# 18_AUDIO_PowerAmp-AnalogT.net
KiCad netlist of a schematic drawn in Altium Designer
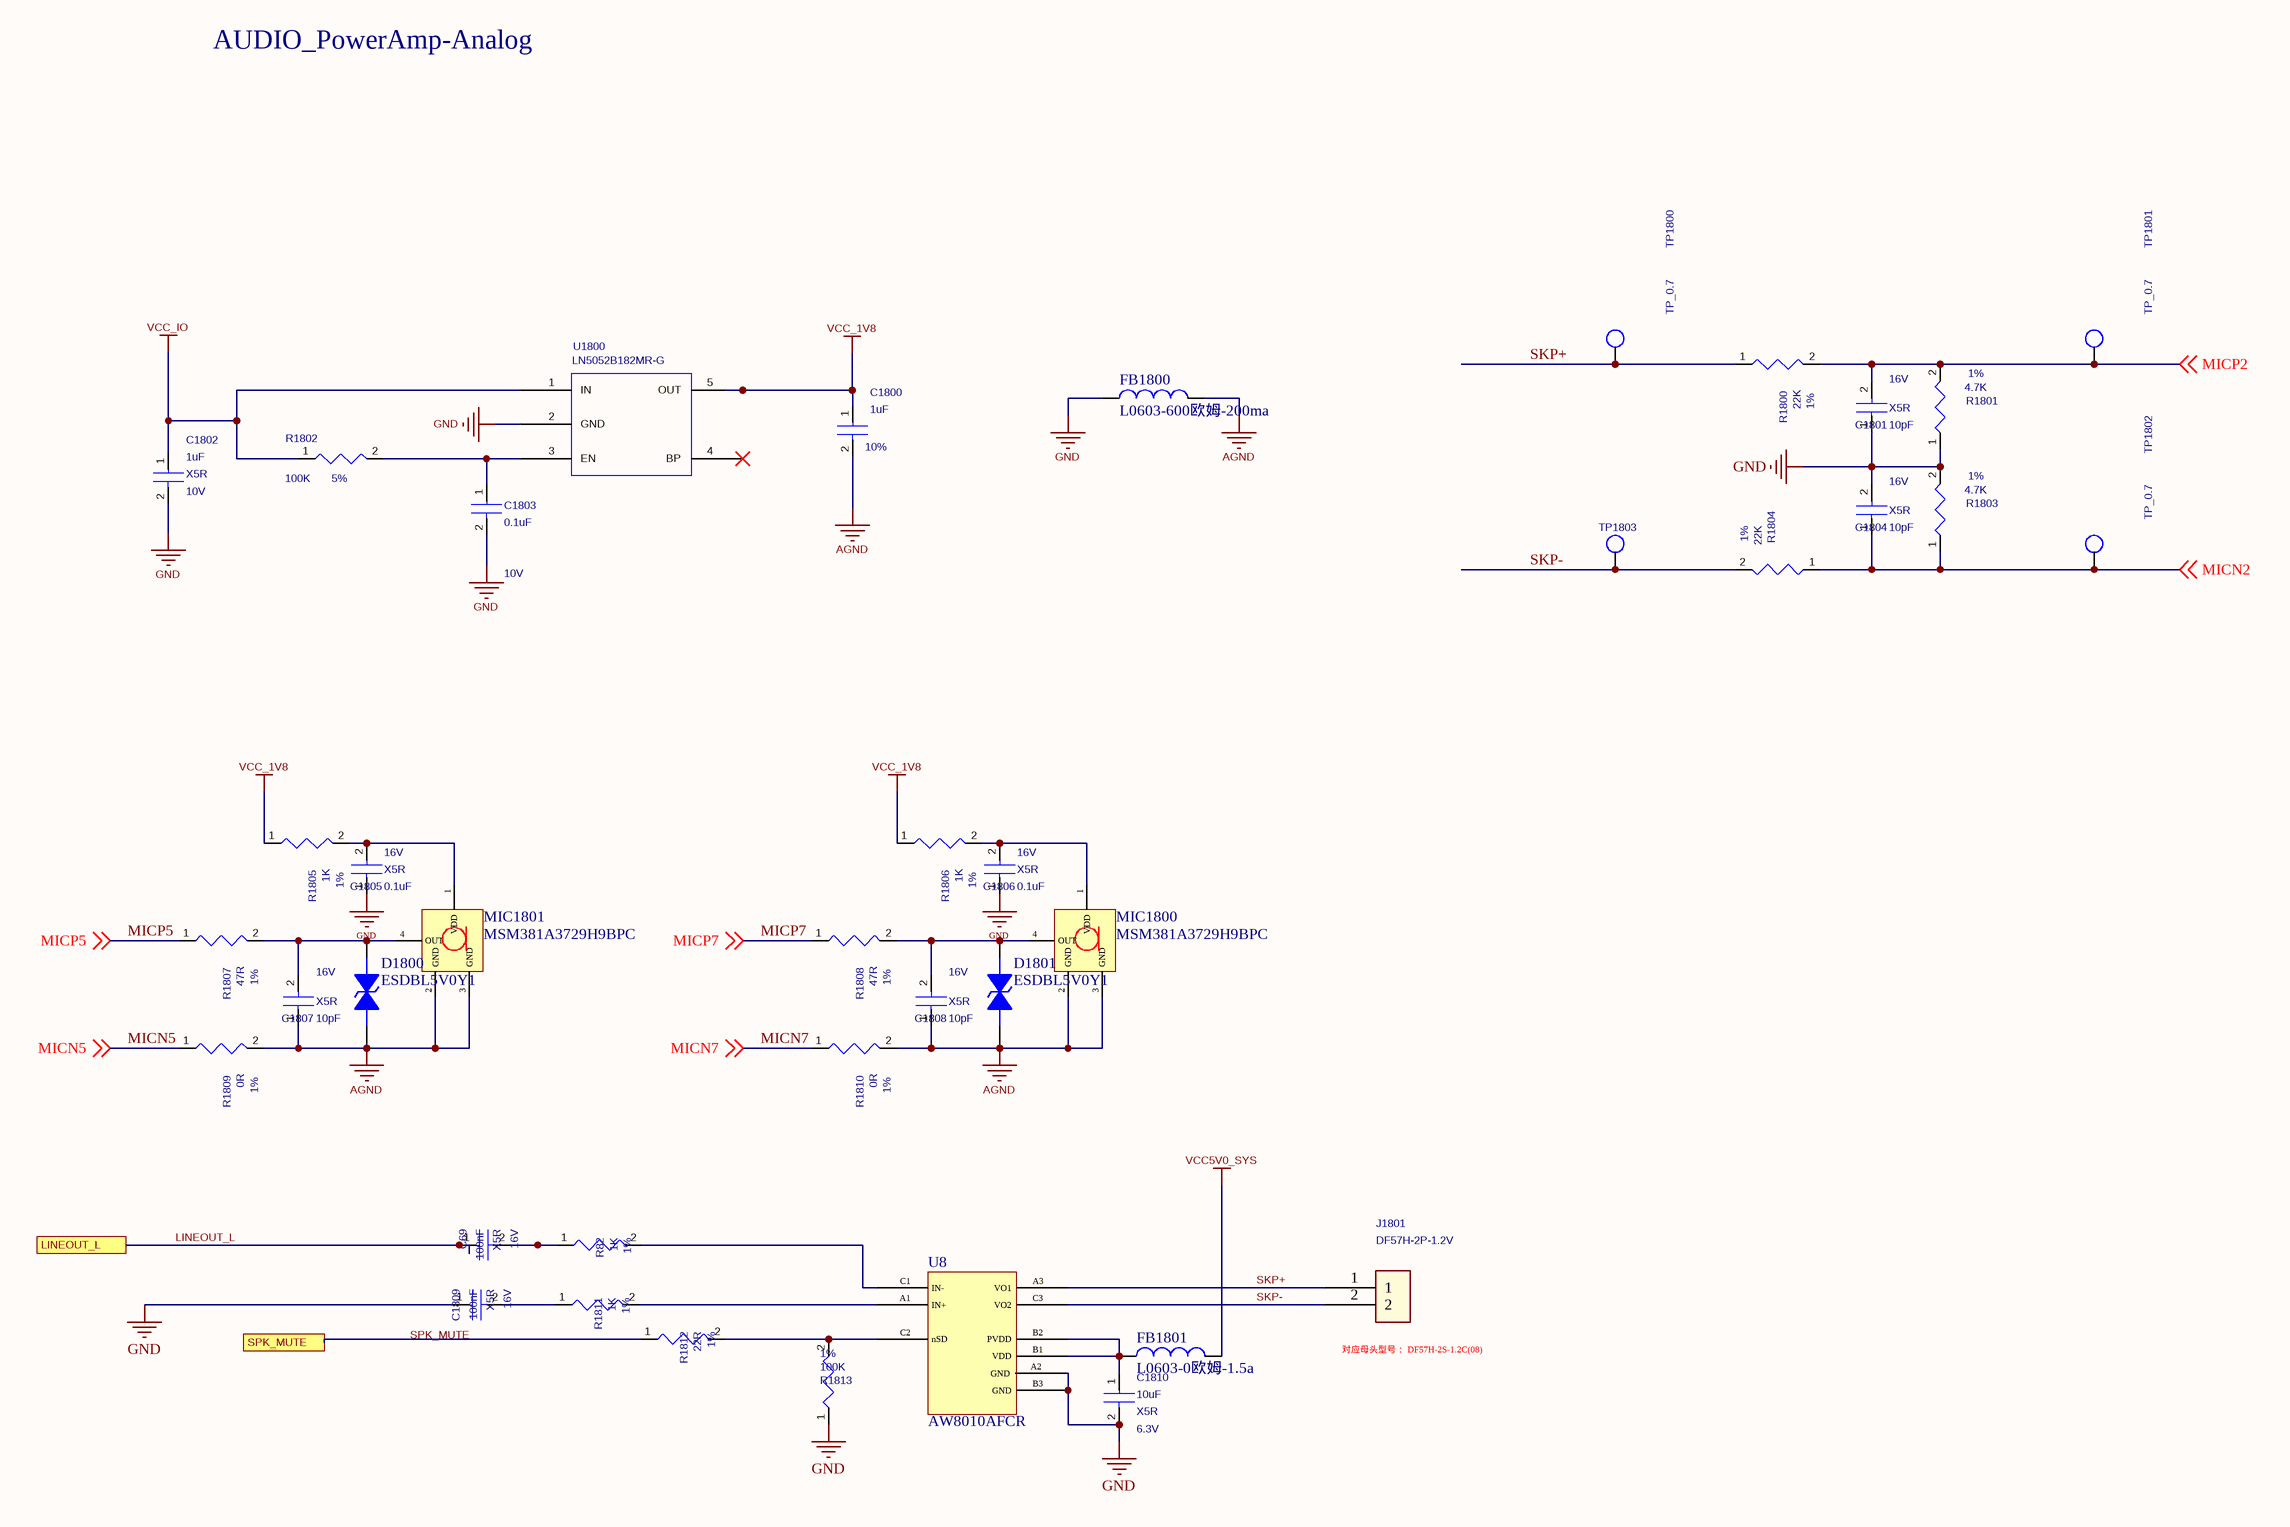
[diagram p0: 18_AUDIO_PowerAmp-AnalogT.SchDoc]

(export (version "E")
  (design (tool "Eeschema 10.0.6"))
  (components
    (comp (ref "C69")
      (value "100nF")
      (footprint "C0402")
      (description "cap,100.00nF,+/-10%,16V,X5R,C0402")
      (fields
        (field (name "MANUFACTURER") "TDK")
        (field (name "TOLERANCE") "10%")
        (field (name "VOLTAGE") "16V")
        (field (name "DIELECTRIC") "X5R")
        (field (name "CREATED_BY") "JJJ")
      )
      (libsource (lib "*") (part "CAP_NP_2"))
    )
    (comp (ref "C1800")
      (value "1uF")
      (footprint "C0402")
      (description "cap,1.00uF,+/-10%,10V,X5R,C0402")
      (fields
        (field (name "VOLTAGE") "10V")
        (field (name "MANUFACTURER") "TDK")
        (field (name "TOLERANCE") "10%")
        (field (name "CREATED_BY") "JJJ")
      )
      (libsource (lib "*") (part "CAP_NP_2"))
    )
    (comp (ref "C1801")
      (value "10pF")
      (footprint "C0402")
      (description "cap,1nF,+/-10%,16V,X5R,C0402")
      (fields
        (field (name "MANUFACTURER") "TDK")
        (field (name "TOLERANCE") "10%")
        (field (name "VOLTAGE") "16V")
        (field (name "DIELECTRIC") "X5R")
        (field (name "CREATED_BY") "JJJ")
      )
      (libsource (lib "*") (part "CAP_NP_2"))
    )
    (comp (ref "C1802")
      (value "1uF")
      (footprint "C0402")
      (description "cap,1.00uF,+/-10%,10V,X5R,C0402")
      (fields
        (field (name "VOLTAGE") "10V")
        (field (name "DIELECTRIC") "X5R")
        (field (name "TOLERANCE") "10%")
        (field (name "MANUFACTURER") "TDK")
        (field (name "CREATED_BY") "JJJ")
      )
      (libsource (lib "*") (part "CAP_NP_2"))
    )
    (comp (ref "C1803")
      (value "0.1uF")
      (footprint "C0402")
      (description "cap,0.1uF,+/-10%,10V,X5R,C0402")
      (fields
        (field (name "TOLERANCE") "10%")
        (field (name "MANUFACTURER") "TDK")
        (field (name "VOLTAGE") "10V")
        (field (name "CREATED_BY") "JJJ")
      )
      (libsource (lib "*") (part "CAP_NP_2"))
    )
    (comp (ref "C1804")
      (value "10pF")
      (footprint "C0402")
      (description "cap,1nF,+/-10%,16V,X5R,C0402")
      (fields
        (field (name "MANUFACTURER") "TDK")
        (field (name "TOLERANCE") "10%")
        (field (name "VOLTAGE") "16V")
        (field (name "DIELECTRIC") "X5R")
        (field (name "CREATED_BY") "JJJ")
      )
      (libsource (lib "*") (part "CAP_NP_2"))
    )
    (comp (ref "C1805")
      (value "0.1uF")
      (footprint "C0402")
      (description "cap,0.1uF,+/-10%,16V,X5R,C0402")
      (fields
        (field (name "MANUFACTURER") "TDK")
        (field (name "TOLERANCE") "10%")
        (field (name "VOLTAGE") "16V")
        (field (name "DIELECTRIC") "X5R")
        (field (name "CREATED_BY") "JJJ")
      )
      (libsource (lib "*") (part "CAP_NP_2"))
    )
    (comp (ref "C1806")
      (value "0.1uF")
      (footprint "C0402")
      (description "cap,0.1uF,+/-10%,16V,X5R,C0402")
      (fields
        (field (name "MANUFACTURER") "TDK")
        (field (name "TOLERANCE") "10%")
        (field (name "VOLTAGE") "16V")
        (field (name "DIELECTRIC") "X5R")
        (field (name "CREATED_BY") "JJJ")
      )
      (libsource (lib "*") (part "CAP_NP_2"))
    )
    (comp (ref "C1807")
      (value "10pF")
      (footprint "C0402")
      (description "cap,10pF,+/-10%,16V,X5R,C0402")
      (fields
        (field (name "MANUFACTURER") "TDK")
        (field (name "TOLERANCE") "10%")
        (field (name "VOLTAGE") "16V")
        (field (name "DIELECTRIC") "X5R")
        (field (name "CREATED_BY") "JJJ")
      )
      (libsource (lib "*") (part "CAP_NP_2"))
    )
    (comp (ref "C1808")
      (value "10pF")
      (footprint "C0402")
      (description "cap,10pF,+/-10%,16V,X5R,C0402")
      (fields
        (field (name "MANUFACTURER") "TDK")
        (field (name "TOLERANCE") "10%")
        (field (name "VOLTAGE") "16V")
        (field (name "DIELECTRIC") "X5R")
        (field (name "CREATED_BY") "JJJ")
      )
      (libsource (lib "*") (part "CAP_NP_2"))
    )
    (comp (ref "C1809")
      (value "100nF")
      (footprint "C0402")
      (description "cap,100.00nF,+/-10%,16V,X5R,C0402")
      (fields
        (field (name "MANUFACTURER") "TDK")
        (field (name "TOLERANCE") "10%")
        (field (name "VOLTAGE") "16V")
        (field (name "DIELECTRIC") "X5R")
        (field (name "CREATED_BY") "JJJ")
      )
      (libsource (lib "*") (part "CAP_NP_2"))
    )
    (comp (ref "C1810")
      (value "10uF")
      (footprint "C0603")
      (description "cap,10.00uF,+/-10%,6.3V,X5R,C0603")
      (fields
        (field (name "DIELECTRIC") "X5R")
        (field (name "VOLTAGE") "6.3V")
        (field (name "TOLERANCE") "10%")
        (field (name "MANUFACTURER") "TDK")
        (field (name "CREATED_BY") "JJJ")
      )
      (libsource (lib "*") (part "CAP_NP_2"))
    )
    (comp (ref "D1800") (value "ESDBL5V0Y1") (footprint "E0402N") (libsource (lib "amenuo") (part "TVS")))
    (comp (ref "D1801") (value "ESDBL5V0Y1") (footprint "E0402N") (libsource (lib "amenuo") (part "TVS")))
    (comp (ref "FB1800")
      (value "L0603-600欧姆-200ma")
      (footprint "L0402")
      (description "L0603-0欧姆-1A")
      (libsource (lib "amenuo") (part "INDUCTOR"))
    )
    (comp (ref "FB1801")
      (value "L0603-0欧姆-1.5a")
      (footprint "L0402")
      (description "L0603-0欧姆-1A")
      (libsource (lib "amenuo") (part "INDUCTOR"))
    )
    (comp (ref "J1801")
      (value "DF57H-2P-1.2V")
      (footprint "PH插座")
      (fields
        (field (name "MANUFACTURER PART NUMBER") "CW2001-02G-S03-C")
        (field (name "MANUFACTURER") "褀华电子")
        (field (name "CREATED BY") "YWQ")
      )
      (libsource (lib "*") (part "CON2_1X2"))
    )
    (comp (ref "MIC1800")
      (value "MSM381A3729H9BPC")
      (footprint "MEMS-4pin")
      (libsource (lib "amenuo") (part "MIC"))
    )
    (comp (ref "MIC1801")
      (value "MSM381A3729H9BPC")
      (footprint "MEMS-4pin")
      (libsource (lib "amenuo") (part "MIC"))
    )
    (comp (ref "R82")
      (value "1K")
      (footprint "R0402")
      (description "?用厚膜电阻,1K,+/-1%,R0402,1/16W.")
      (fields
        (field (name "MANUFACTURER") "YAGEO")
        (field (name "TOLERANCE") "1%")
        (field (name "Comment") "RESISTOR")
        (field (name "CREATED_BY") "YTL")
      )
      (libsource (lib "*") (part "RESISTOR"))
    )
    (comp (ref "R1800")
      (value "22K")
      (footprint "R0402")
      (description "?用厚膜电阻,22K,+/-1%,R0402,1/16W.")
      (fields
        (field (name "MANUFACTURER") "YAGEO")
        (field (name "TOLERANCE") "1%")
        (field (name "Comment") "RESISTOR")
        (field (name "CREATED_BY") "YTL")
      )
      (libsource (lib "*") (part "RESISTOR"))
    )
    (comp (ref "R1801")
      (value "4.7K")
      (footprint "R0402")
      (description "?用厚膜电阻,4.7K+/-1%,R0402,1/16W.")
      (fields
        (field (name "MANUFACTURER") "YAGEO")
        (field (name "TOLERANCE") "1%")
        (field (name "Comment") "RESISTOR")
        (field (name "CREATED_BY") "YTL")
      )
      (libsource (lib "*") (part "RESISTOR"))
    )
    (comp (ref "R1802")
      (value "100K")
      (footprint "R0402")
      (description "?用厚膜电阻,100K,+/-5%,R0402,1/16W.")
      (fields
        (field (name "TOLERANCE") "5%")
        (field (name "MANUFACTURER") "YAGEO")
        (field (name "Comment") "RESISTOR")
        (field (name "CREATED_BY") "YTL")
      )
      (libsource (lib "*") (part "RESISTOR"))
    )
    (comp (ref "R1803")
      (value "4.7K")
      (footprint "R0402")
      (description "?用厚膜电阻,4.7K,+/-1%,R0402,1/16W.")
      (fields
        (field (name "MANUFACTURER") "YAGEO")
        (field (name "TOLERANCE") "1%")
        (field (name "Comment") "RESISTOR")
        (field (name "CREATED_BY") "YTL")
      )
      (libsource (lib "*") (part "RESISTOR"))
    )
    (comp (ref "R1804")
      (value "22K")
      (footprint "R0402")
      (description "?用厚膜电阻,22K,+/-1%,R0402,1/16W.")
      (fields
        (field (name "MANUFACTURER") "YAGEO")
        (field (name "TOLERANCE") "1%")
        (field (name "Comment") "RESISTOR")
        (field (name "CREATED_BY") "YTL")
      )
      (libsource (lib "*") (part "RESISTOR"))
    )
    (comp (ref "R1805")
      (value "1K")
      (footprint "R0402")
      (description "?用厚膜电阻,1K,+/-1%,R0402,1/16W.")
      (fields
        (field (name "MANUFACTURER") "YAGEO")
        (field (name "TOLERANCE") "1%")
        (field (name "Comment") "RESISTOR")
        (field (name "CREATED_BY") "YTL")
      )
      (libsource (lib "*") (part "RESISTOR"))
    )
    (comp (ref "R1806")
      (value "1K")
      (footprint "R0402")
      (description "?用厚膜电阻,1K,+/-1%,R0402,1/16W.")
      (fields
        (field (name "MANUFACTURER") "YAGEO")
        (field (name "TOLERANCE") "1%")
        (field (name "Comment") "RESISTOR")
        (field (name "CREATED_BY") "YTL")
      )
      (libsource (lib "*") (part "RESISTOR"))
    )
    (comp (ref "R1807")
      (value "47R")
      (footprint "R0402")
      (description "?用厚膜电阻,47R,+/-1%,R0402,1/16W.")
      (fields
        (field (name "MANUFACTURER") "YAGEO")
        (field (name "TOLERANCE") "1%")
        (field (name "Comment") "RESISTOR")
        (field (name "CREATED_BY") "YTL")
      )
      (libsource (lib "*") (part "RESISTOR"))
    )
    (comp (ref "R1808")
      (value "47R")
      (footprint "R0402")
      (description "?用厚膜电阻,47R,+/-1%,R0402,1/16W.")
      (fields
        (field (name "MANUFACTURER") "YAGEO")
        (field (name "TOLERANCE") "1%")
        (field (name "Comment") "RESISTOR")
        (field (name "CREATED_BY") "YTL")
      )
      (libsource (lib "*") (part "RESISTOR"))
    )
    (comp (ref "R1809")
      (value "0R")
      (footprint "R0402")
      (description "?用厚膜电阻,0R,+/-1%,R0402,1/16W.")
      (fields
        (field (name "MANUFACTURER") "YAGEO")
        (field (name "TOLERANCE") "1%")
        (field (name "Comment") "RESISTOR")
        (field (name "CREATED_BY") "YTL")
      )
      (libsource (lib "*") (part "RESISTOR"))
    )
    (comp (ref "R1810")
      (value "0R")
      (footprint "R0402")
      (description "?用厚膜电阻,0R,+/-1%,R0402,1/16W.")
      (fields
        (field (name "MANUFACTURER") "YAGEO")
        (field (name "TOLERANCE") "1%")
        (field (name "Comment") "RESISTOR")
        (field (name "CREATED_BY") "YTL")
      )
      (libsource (lib "*") (part "RESISTOR"))
    )
    (comp (ref "R1811")
      (value "1K")
      (footprint "R0402")
      (description "?用厚膜电阻,1K,+/-1%,R0402,1/16W.")
      (fields
        (field (name "MANUFACTURER") "YAGEO")
        (field (name "TOLERANCE") "1%")
        (field (name "Comment") "RESISTOR")
        (field (name "CREATED_BY") "YTL")
      )
      (libsource (lib "*") (part "RESISTOR"))
    )
    (comp (ref "R1812")
      (value "22R")
      (footprint "R0402")
      (description "?用厚膜电阻,22R,+/-1%,R0402,1/16W.")
      (fields
        (field (name "MANUFACTURER") "YAGEO")
        (field (name "TOLERANCE") "1%")
        (field (name "Comment") "RESISTOR")
        (field (name "CREATED_BY") "YTL")
      )
      (libsource (lib "*") (part "RESISTOR"))
    )
    (comp (ref "R1813")
      (value "100K")
      (footprint "R0402")
      (description "?用厚膜电阻,100K,+/-1%,R0402,1/16W.")
      (fields
        (field (name "MANUFACTURER") "YAGEO")
        (field (name "TOLERANCE") "1%")
        (field (name "Comment") "RESISTOR")
        (field (name "CREATED_BY") "YTL")
      )
      (libsource (lib "*") (part "RESISTOR"))
    )
    (comp (ref "TP1800")
      (value "TP_0.7")
      (footprint "TEST")
      (description "Test Point 0.7mm")
      (fields (field (name "CREATED BY") "JJJ"))
      (libsource (lib "*") (part "TP"))
    )
    (comp (ref "TP1801")
      (value "TP_0.7")
      (footprint "TEST")
      (description "Test Point 0.7mm")
      (fields (field (name "CREATED BY") "JJJ"))
      (libsource (lib "*") (part "TP"))
    )
    (comp (ref "TP1802")
      (value "TP_0.7")
      (footprint "TEST")
      (description "Test Point 0.7mm")
      (fields (field (name "CREATED BY") "JJJ"))
      (libsource (lib "*") (part "TP"))
    )
    (comp (ref "TP1803")
      (value "TP_0.7")
      (footprint "TEST")
      (description "Test Point 0.7mm")
      (fields (field (name "CREATED BY") "JJJ"))
      (libsource (lib "*") (part "TP"))
    )
    (comp (ref "U8") (value "AW8010AFCR") (footprint "FC-9") (libsource (lib "amenuo") (part "U")))
    (comp (ref "U1800")
      (value "LN5052B182MR-G")
      (footprint "SOT_23_5")
      (description "High-PSRR 600mA LDO.Output1.8V.")
      (fields (field (name "MANUFACTURER") "Powtech(华润矽威）") (field (name "CREATED_BY") "JJJ"))
      (libsource (lib "*") (part "LDO_PT5108"))
    )
  )
  (nets
    (net (code "1") (name "/LINEOUT_L") (class "Default")
      (node (ref "C69") (pin "1") (pinfunction "1_1") (pintype "passive"))
    )
    (net (code "2") (name "/SKP+") (class "Default")
      (node (ref "J1801") (pin "1") (pinfunction "1_1") (pintype "passive"))
      (node (ref "R1800") (pin "1") (pinfunction "1_1") (pintype "passive"))
      (node (ref "TP1800") (pin "1") (pinfunction "1_1") (pintype "passive"))
      (node (ref "U8") (pin "A3") (pinfunction "VO1_A3") (pintype "passive"))
    )
    (net (code "3") (name "/SKP-") (class "Default")
      (node (ref "J1801") (pin "2") (pinfunction "2_2") (pintype "passive"))
      (node (ref "R1804") (pin "2") (pinfunction "2_2") (pintype "passive"))
      (node (ref "TP1803") (pin "1") (pinfunction "1_1") (pintype "passive"))
      (node (ref "U8") (pin "C3") (pinfunction "VO2_C3") (pintype "passive"))
    )
    (net (code "4") (name "/SPK_MUTE") (class "Default")
      (node (ref "R1812") (pin "1") (pinfunction "1_1") (pintype "passive"))
    )
    (net (code "5") (name "AGND") (class "Default")
      (node (ref "C1800") (pin "2") (pinfunction "2_2") (pintype "passive"))
      (node (ref "C1807") (pin "1") (pinfunction "1_1") (pintype "passive"))
      (node (ref "C1808") (pin "1") (pinfunction "1_1") (pintype "passive"))
      (node (ref "D1800") (pin "1") (pinfunction "1_1") (pintype "passive"))
      (node (ref "D1801") (pin "1") (pinfunction "1_1") (pintype "passive"))
      (node (ref "FB1800") (pin "2") (pinfunction "2_2") (pintype "passive"))
      (node (ref "MIC1800") (pin "2") (pinfunction "GND_2") (pintype "passive"))
      (node (ref "MIC1800") (pin "3") (pinfunction "GND_3") (pintype "passive"))
      (node (ref "MIC1801") (pin "2") (pinfunction "GND_2") (pintype "passive"))
      (node (ref "MIC1801") (pin "3") (pinfunction "GND_3") (pintype "passive"))
      (node (ref "R1809") (pin "2") (pinfunction "2_2") (pintype "passive"))
      (node (ref "R1810") (pin "2") (pinfunction "2_2") (pintype "passive"))
    )
    (net (code "6") (name "GND") (class "Default")
      (node (ref "C1801") (pin "1") (pinfunction "1_1") (pintype "passive"))
      (node (ref "C1802") (pin "2") (pinfunction "2_2") (pintype "passive"))
      (node (ref "C1803") (pin "2") (pinfunction "2_2") (pintype "passive"))
      (node (ref "C1804") (pin "2") (pinfunction "2_2") (pintype "passive"))
      (node (ref "C1805") (pin "1") (pinfunction "1_1") (pintype "passive"))
      (node (ref "C1806") (pin "1") (pinfunction "1_1") (pintype "passive"))
      (node (ref "C1809") (pin "1") (pinfunction "1_1") (pintype "passive"))
      (node (ref "C1810") (pin "2") (pinfunction "2_2") (pintype "passive"))
      (node (ref "FB1800") (pin "1") (pinfunction "1_1") (pintype "passive"))
      (node (ref "R1801") (pin "1") (pinfunction "1_1") (pintype "passive"))
      (node (ref "R1803") (pin "2") (pinfunction "2_2") (pintype "passive"))
      (node (ref "R1813") (pin "1") (pinfunction "1_1") (pintype "passive"))
      (node (ref "U1800") (pin "2") (pinfunction "GND_2") (pintype "passive"))
      (node (ref "U8") (pin "A2") (pinfunction "GND_A2") (pintype "passive"))
      (node (ref "U8") (pin "B3") (pinfunction "GND_B3") (pintype "passive"))
    )
    (net (code "7") (name "MICN2") (class "Default")
      (node (ref "C1804") (pin "1") (pinfunction "1_1") (pintype "passive"))
      (node (ref "R1803") (pin "1") (pinfunction "1_1") (pintype "passive"))
      (node (ref "R1804") (pin "1") (pinfunction "1_1") (pintype "passive"))
      (node (ref "TP1802") (pin "1") (pinfunction "1_1") (pintype "passive"))
    )
    (net (code "8") (name "MICN5") (class "Default")
      (node (ref "R1809") (pin "1") (pinfunction "1_1") (pintype "passive"))
    )
    (net (code "9") (name "MICN7") (class "Default")
      (node (ref "R1810") (pin "1") (pinfunction "1_1") (pintype "passive"))
    )
    (net (code "10") (name "MICP2") (class "Default")
      (node (ref "C1801") (pin "2") (pinfunction "2_2") (pintype "passive"))
      (node (ref "R1800") (pin "2") (pinfunction "2_2") (pintype "passive"))
      (node (ref "R1801") (pin "2") (pinfunction "2_2") (pintype "passive"))
      (node (ref "TP1801") (pin "1") (pinfunction "1_1") (pintype "passive"))
    )
    (net (code "11") (name "MICP5") (class "Default")
      (node (ref "R1807") (pin "1") (pinfunction "1_1") (pintype "passive"))
    )
    (net (code "12") (name "MICP7") (class "Default")
      (node (ref "R1808") (pin "1") (pinfunction "1_1") (pintype "passive"))
    )
    (net (code "13") (name "Net-(C69-Pad2)") (class "Default")
      (node (ref "C69") (pin "2") (pinfunction "2_2") (pintype "passive"))
      (node (ref "R82") (pin "1") (pinfunction "1_1") (pintype "passive"))
    )
    (net (code "14") (name "Net-(C1809-Pad2)") (class "Default")
      (node (ref "C1809") (pin "2") (pinfunction "2_2") (pintype "passive"))
      (node (ref "R1811") (pin "1") (pinfunction "1_1") (pintype "passive"))
    )
    (net (code "15") (name "Net-(MIC1800-OUT)") (class "Default")
      (node (ref "C1808") (pin "2") (pinfunction "2_2") (pintype "passive"))
      (node (ref "D1801") (pin "2") (pinfunction "2_2") (pintype "passive"))
      (node (ref "MIC1800") (pin "4") (pinfunction "OUT_4") (pintype "passive"))
      (node (ref "R1808") (pin "2") (pinfunction "2_2") (pintype "passive"))
    )
    (net (code "16") (name "Net-(MIC1800-VDD)") (class "Default")
      (node (ref "C1806") (pin "2") (pinfunction "2_2") (pintype "passive"))
      (node (ref "MIC1800") (pin "1") (pinfunction "VDD_1") (pintype "passive"))
      (node (ref "R1806") (pin "2") (pinfunction "2_2") (pintype "passive"))
    )
    (net (code "17") (name "Net-(MIC1801-OUT)") (class "Default")
      (node (ref "C1807") (pin "2") (pinfunction "2_2") (pintype "passive"))
      (node (ref "D1800") (pin "2") (pinfunction "2_2") (pintype "passive"))
      (node (ref "MIC1801") (pin "4") (pinfunction "OUT_4") (pintype "passive"))
      (node (ref "R1807") (pin "2") (pinfunction "2_2") (pintype "passive"))
    )
    (net (code "18") (name "Net-(MIC1801-VDD)") (class "Default")
      (node (ref "C1805") (pin "2") (pinfunction "2_2") (pintype "passive"))
      (node (ref "MIC1801") (pin "1") (pinfunction "VDD_1") (pintype "passive"))
      (node (ref "R1805") (pin "2") (pinfunction "2_2") (pintype "passive"))
    )
    (net (code "19") (name "Net-(U8-IN+)") (class "Default")
      (node (ref "R1811") (pin "2") (pinfunction "2_2") (pintype "passive"))
      (node (ref "U8") (pin "A1") (pinfunction "IN+_A1") (pintype "passive"))
    )
    (net (code "20") (name "Net-(U8-IN-)") (class "Default")
      (node (ref "R82") (pin "2") (pinfunction "2_2") (pintype "passive"))
      (node (ref "U8") (pin "C1") (pinfunction "IN-_C1") (pintype "passive"))
    )
    (net (code "21") (name "Net-(U8-PVDD)") (class "Default")
      (node (ref "C1810") (pin "1") (pinfunction "1_1") (pintype "passive"))
      (node (ref "FB1801") (pin "1") (pinfunction "1_1") (pintype "passive"))
      (node (ref "U8") (pin "B1") (pinfunction "VDD_B1") (pintype "passive"))
      (node (ref "U8") (pin "B2") (pinfunction "PVDD_B2") (pintype "passive"))
    )
    (net (code "22") (name "Net-(U8-nSD)") (class "Default")
      (node (ref "R1812") (pin "2") (pinfunction "2_2") (pintype "passive"))
      (node (ref "R1813") (pin "2") (pinfunction "2_2") (pintype "passive"))
      (node (ref "U8") (pin "C2") (pinfunction "nSD_C2") (pintype "passive"))
    )
    (net (code "23") (name "Net-(U1800-EN)") (class "Default")
      (node (ref "C1803") (pin "1") (pinfunction "1_1") (pintype "passive"))
      (node (ref "R1802") (pin "2") (pinfunction "2_2") (pintype "passive"))
      (node (ref "U1800") (pin "3") (pinfunction "EN_3") (pintype "passive"))
    )
    (net (code "24") (name "VCC5V0_SYS") (class "Default")
      (node (ref "FB1801") (pin "2") (pinfunction "2_2") (pintype "passive"))
    )
    (net (code "25") (name "VCC_1V8") (class "Default")
      (node (ref "C1800") (pin "1") (pinfunction "1_1") (pintype "passive"))
      (node (ref "R1805") (pin "1") (pinfunction "1_1") (pintype "passive"))
      (node (ref "R1806") (pin "1") (pinfunction "1_1") (pintype "passive"))
      (node (ref "U1800") (pin "5") (pinfunction "OUT_5") (pintype "passive"))
    )
    (net (code "26") (name "VCC_IO") (class "Default")
      (node (ref "C1802") (pin "1") (pinfunction "1_1") (pintype "passive"))
      (node (ref "R1802") (pin "1") (pinfunction "1_1") (pintype "passive"))
      (node (ref "U1800") (pin "1") (pinfunction "IN_1") (pintype "passive"))
    )
    (net (code "27") (name "unconnected-(U1800-BP-Pad4)") (class "Default")
      (node (ref "U1800") (pin "4") (pinfunction "BP_4") (pintype "passive+no_connect"))
    )
  )
)
